# NMX-202.net
KiCad netlist of a schematic drawn in EAGLE
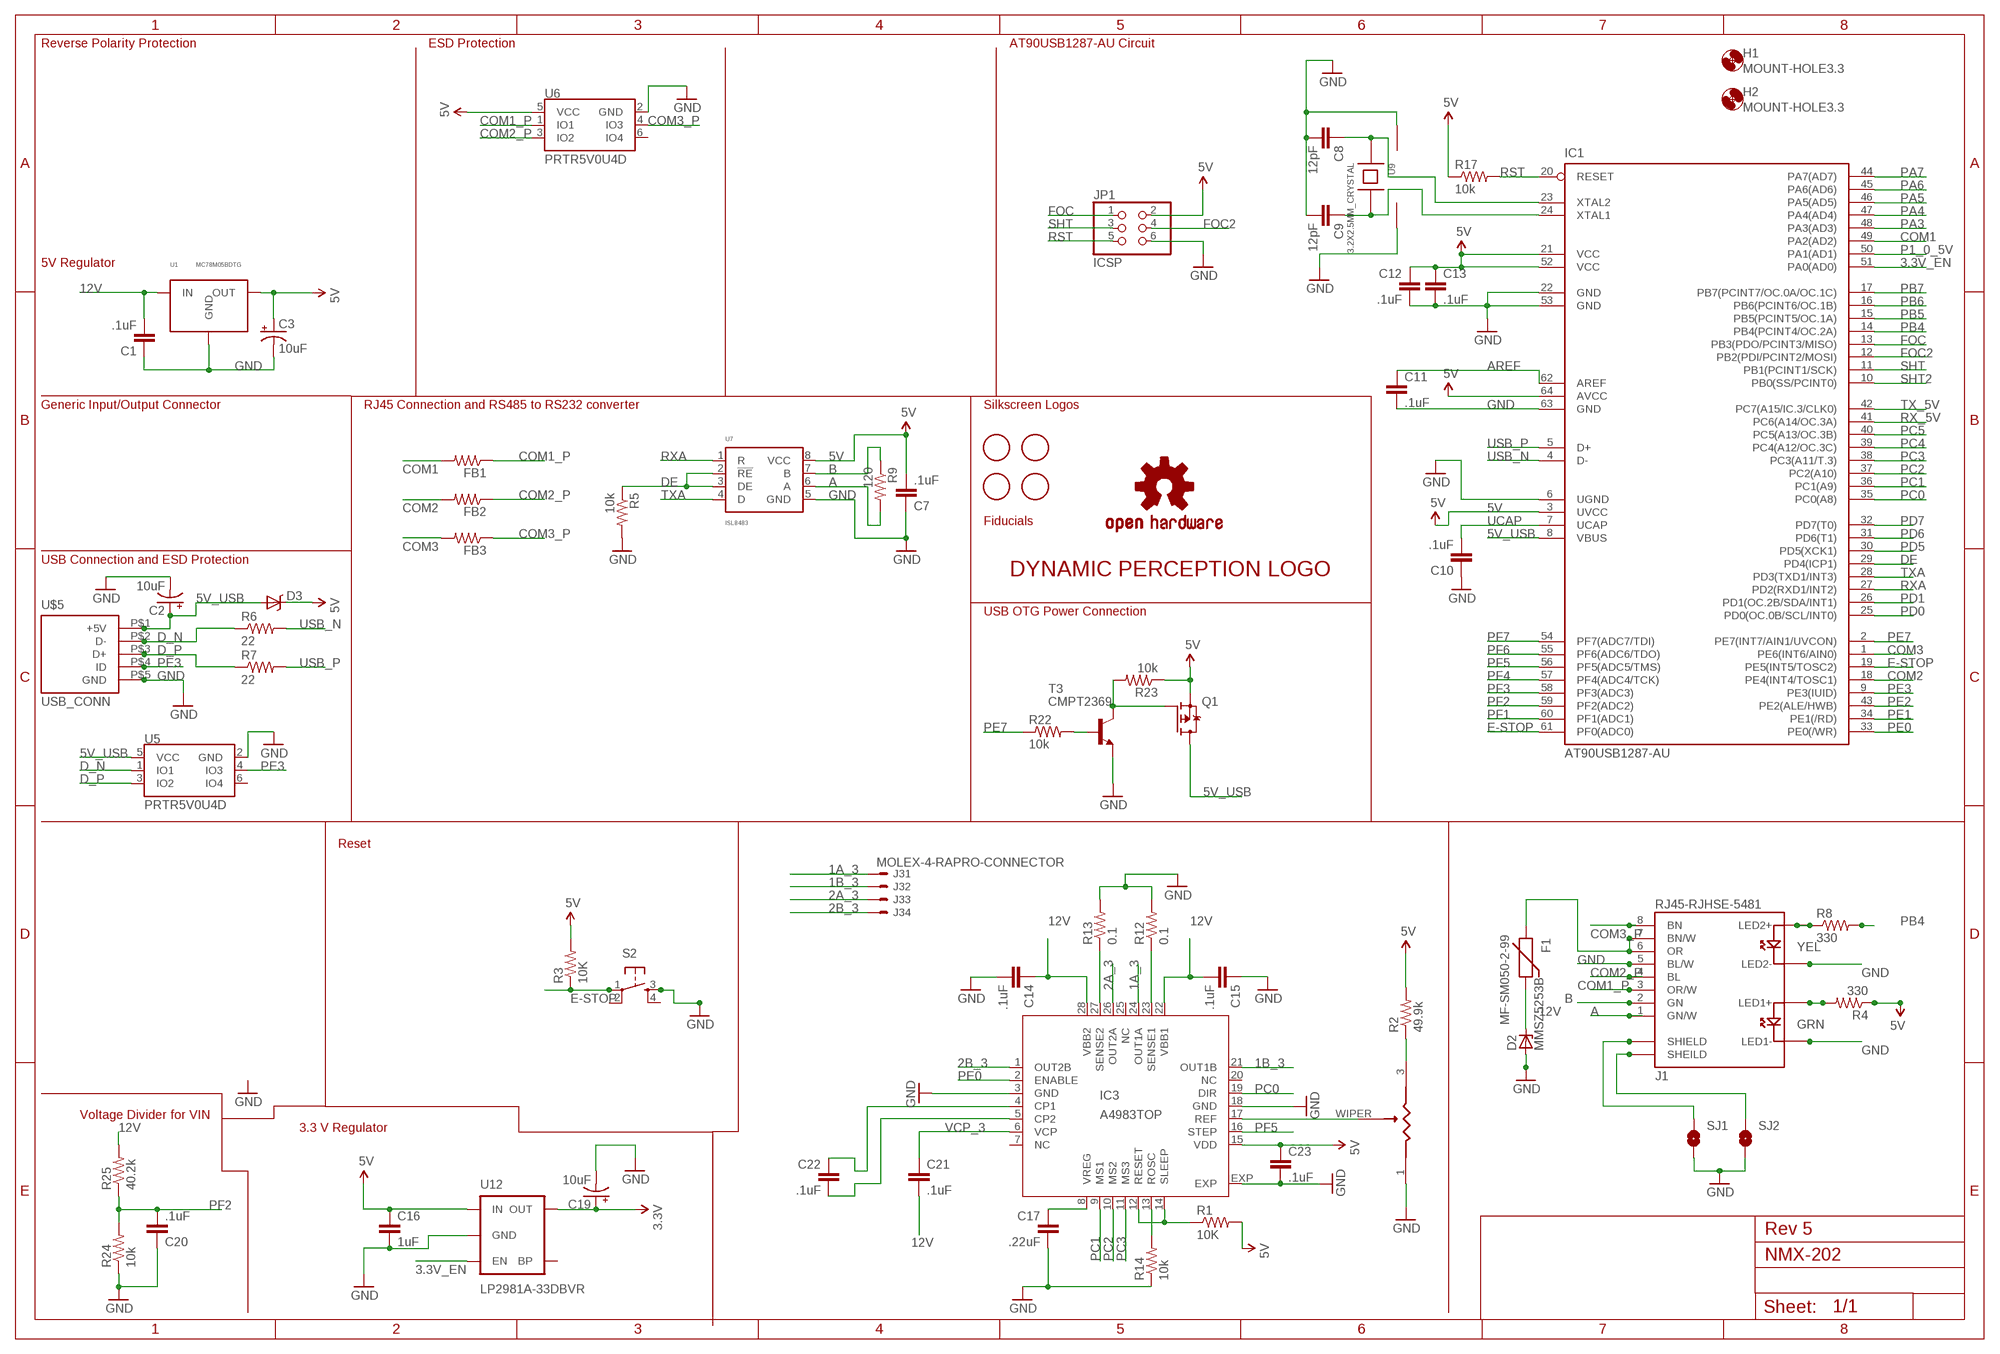
[diagram p0: schematic, sheet 1]

(export (version "E")
  (design (tool "Eeschema 10.0.6"))
  (components
    (comp (ref "C1")
      (value ".1uF")
      (footprint "eagle-import:0402-CAP")
      (fields (field (name "MF") "Taiyo Yuden") (field (name "MPN") "TMK105BJ104KV-F"))
      (libsource (lib "eagle-import") (part "CAP0402-CAP"))
    )
    (comp (ref "C2")
      (value "10uF")
      (footprint "eagle-import:EIA3216")
      (fields (field (name "MF") "Kemet") (field (name "MPN") "T491A106M016AT"))
      (libsource (lib "eagle-import") (part "CAP_POL1206"))
    )
    (comp (ref "C3")
      (value "10uF")
      (footprint "eagle-import:EIA3216")
      (fields (field (name "MF") "Kemet") (field (name "MPN") "T491A106M016AT"))
      (libsource (lib "eagle-import") (part "CAP_POL1206"))
    )
    (comp (ref "C7")
      (value ".1uF")
      (footprint "eagle-import:0402-CAP")
      (fields (field (name "MF") "Taiyo Yuden") (field (name "MPN") "TMK105BJ104KV-F"))
      (libsource (lib "eagle-import") (part "CAP0402-CAP"))
    )
    (comp (ref "C8")
      (value "12pF")
      (footprint "eagle-import:0402-CAP")
      (fields (field (name "MF") "TDK Corporation") (field (name "MPN") "C1005C0G1H120J050BA"))
      (libsource (lib "eagle-import") (part "CAP0402-CAP"))
    )
    (comp (ref "C9")
      (value "12pF")
      (footprint "eagle-import:0402-CAP")
      (fields (field (name "MF") "TDK Corporation") (field (name "MPN") "C1005C0G1H120J050BA"))
      (libsource (lib "eagle-import") (part "CAP0402-CAP"))
    )
    (comp (ref "C10")
      (value ".1uF")
      (footprint "eagle-import:0402-CAP")
      (fields (field (name "MF") "Taiyo Yuden") (field (name "MPN") "TMK105BJ104KV-F"))
      (libsource (lib "eagle-import") (part "CAP0402-CAP"))
    )
    (comp (ref "C11")
      (value ".1uF")
      (footprint "eagle-import:0402-CAP")
      (fields (field (name "MF") "Taiyo Yuden") (field (name "MPN") "TMK105BJ104KV-F"))
      (libsource (lib "eagle-import") (part "CAP0402-CAP"))
    )
    (comp (ref "C12")
      (value ".1uF")
      (footprint "eagle-import:0402-CAP")
      (fields (field (name "MF") "Taiyo Yuden") (field (name "MPN") "TMK105BJ104KV-F"))
      (libsource (lib "eagle-import") (part "CAP0402-CAP"))
    )
    (comp (ref "C13")
      (value ".1uF")
      (footprint "eagle-import:0402-CAP")
      (fields (field (name "MF") "Taiyo Yuden") (field (name "MPN") "TMK105BJ104KV-F"))
      (libsource (lib "eagle-import") (part "CAP0402-CAP"))
    )
    (comp (ref "C14")
      (value ".1uF")
      (footprint "eagle-import:0402-CAP")
      (fields (field (name "MF") "Taiyo Yuden") (field (name "MPN") "TMK105BJ104KV-F"))
      (libsource (lib "eagle-import") (part "CAP0402-CAP"))
    )
    (comp (ref "C15")
      (value ".1uF")
      (footprint "eagle-import:0402-CAP")
      (fields (field (name "MF") "Taiyo Yuden") (field (name "MPN") "TMK105BJ104KV-F"))
      (libsource (lib "eagle-import") (part "CAP0402-CAP"))
    )
    (comp (ref "C16")
      (value "1uF")
      (footprint "eagle-import:0402-CAP")
      (fields (field (name "MF") "TDK Corporation") (field (name "MPN") "C1005X5R1C105K050BC"))
      (libsource (lib "eagle-import") (part "CAP0402-CAP"))
    )
    (comp (ref "C17")
      (value ".22uF")
      (footprint "eagle-import:0402-CAP")
      (fields (field (name "MF") "Taiyo Yuden") (field (name "MPN") "TMK105BJ224KVHF"))
      (libsource (lib "eagle-import") (part "CAP0402-CAP"))
    )
    (comp (ref "C19")
      (value "10uF")
      (footprint "eagle-import:EIA3216")
      (fields (field (name "MF") "Kemet") (field (name "MPN") "T491A106M016AT"))
      (libsource (lib "eagle-import") (part "CAP_POL1206"))
    )
    (comp (ref "C20")
      (value ".1uF")
      (footprint "eagle-import:0402-CAP")
      (fields (field (name "MF") "Taiyo Yuden") (field (name "MPN") "TMK105BJ104KV-F"))
      (libsource (lib "eagle-import") (part "CAP0402-CAP"))
    )
    (comp (ref "C21")
      (value ".1uF")
      (footprint "eagle-import:0402-CAP")
      (fields (field (name "MF") "Taiyo Yuden") (field (name "MPN") "TMK105BJ104KV-F"))
      (libsource (lib "eagle-import") (part "CAP0402-CAP"))
    )
    (comp (ref "C22")
      (value ".1uF")
      (footprint "eagle-import:0402-CAP")
      (fields (field (name "MF") "Taiyo Yuden") (field (name "MPN") "TMK105BJ104KV-F"))
      (libsource (lib "eagle-import") (part "CAP0402-CAP"))
    )
    (comp (ref "C23")
      (value ".1uF")
      (footprint "eagle-import:0402-CAP")
      (fields (field (name "MF") "Taiyo Yuden") (field (name "MPN") "TMK105BJ104KV-F"))
      (libsource (lib "eagle-import") (part "CAP0402-CAP"))
    )
    (comp (ref "D2")
      (value "MMSZ5253B")
      (footprint "eagle-import:SOD123")
      (fields (field (name "MF") "Fairchild Semiconductor"))
      (libsource (lib "eagle-import") (part "ZENER-DIODESOD123"))
    )
    (comp (ref "D3")
      (value "DIODE-SCHOTTKY-BAT20J")
      (footprint "eagle-import:SOD-323")
      (fields (field (name "MF") "NXP Semiconductors") (field (name "MPN") "PMEG3010BEA,115"))
      (libsource (lib "eagle-import") (part "DIODE-SCHOTTKY-BAT20J"))
    )
    (comp (ref "F1")
      (value "MF-SM050-2-99")
      (footprint "eagle-import:PTC-2920")
      (fields (field (name "MF") "Bel Fuse") (field (name "MPN") "0ZCD0050FF2C"))
      (libsource (lib "eagle-import") (part "PTC2920"))
    )
    (comp (ref "FB1")
      (value "HZ0402B102R-10")
      (footprint "eagle-import:R0402")
      (fields (field (name "MF") "Laird-Signal Integrity Products"))
      (libsource (lib "eagle-import") (part "R-US_R0402"))
    )
    (comp (ref "FB2")
      (value "HZ0402B102R-10")
      (footprint "eagle-import:R0402")
      (fields (field (name "MF") "Laird-Signal Integrity Products"))
      (libsource (lib "eagle-import") (part "R-US_R0402"))
    )
    (comp (ref "FB3")
      (value "HZ0402B102R-10")
      (footprint "eagle-import:R0402")
      (fields (field (name "MF") "Laird-Signal Integrity Products"))
      (libsource (lib "eagle-import") (part "R-US_R0402"))
    )
    (comp (ref "FRAME2")
      (value "A3L-LOCSILK_SCREEN")
      (footprint "eagle-import:DRAWING_NAME")
      (libsource (lib "eagle-import") (part "A3L-LOCSILK_SCREEN"))
    )
    (comp (ref "H1")
      (value "MOUNT-HOLE3.3")
      (footprint "eagle-import:3,3")
      (libsource (lib "eagle-import") (part "MOUNT-HOLE3.3"))
    )
    (comp (ref "H2")
      (value "MOUNT-HOLE3.3")
      (footprint "eagle-import:3,3")
      (libsource (lib "eagle-import") (part "MOUNT-HOLE3.3"))
    )
    (comp (ref "IC1")
      (value "AT90USB1287-AU")
      (footprint "eagle-import:TQFP64")
      (fields (field (name "MF") "Atmel"))
      (libsource (lib "eagle-import") (part "AT90USB1287-AU"))
    )
    (comp (ref "IC3")
      (value "A4983TOP")
      (footprint "eagle-import:QFN28ET")
      (fields (field (name "MPN") "A4983SETTR-T") (field (name "MPN_1") "A4983SETTR-T"))
      (libsource (lib "eagle-import") (part "A4983TOP"))
    )
    (comp (ref "J1")
      (value "RJ45-RJHSE-5481")
      (footprint "eagle-import:RJ45-RJHSE")
      (libsource (lib "eagle-import") (part "RJ45-RJHSE-5481"))
    )
    (comp (ref "J3")
      (value "MOLEX-4-RAPRO-CONNECTOR")
      (footprint "eagle-import:PRO_CONNECTOR")
      (fields (field (name "MF") "Molex Inc") (field (name "MPN") "0022053041"))
      (libsource (lib "eagle-import") (part "MOLEX-4-RAPRO-CONNECTOR"))
    )
    (comp (ref "JP1")
      (value "ICSP")
      (footprint "eagle-import:2X03")
      (fields (field (name "MF") "FCI") (field (name "MPN") "67996-406HLF"))
      (libsource (lib "eagle-import") (part "PINHD-2X3"))
    )
    (comp (ref "Q1")
      (value "P-CHANNEL_MOSFET")
      (footprint "eagle-import:SOT23-3")
      (fields (field (name "MF") "Fairchild Semiconductor") (field (name "MPN") "FDV304P"))
      (libsource (lib "eagle-import") (part "P-CHANNEL_MOSFET"))
    )
    (comp (ref "R1")
      (value "10K")
      (footprint "eagle-import:R0402_BOTTOM")
      (fields (field (name "MF") "Yageo") (field (name "MPN") "RC0402FR-0710KL"))
      (libsource (lib "eagle-import") (part "R-US_R0402_B"))
    )
    (comp (ref "R2")
      (value "49.9k")
      (footprint "eagle-import:R0402_BOTTOM")
      (fields (field (name "MF") "Yageo") (field (name "MPN") "RC0402FR-0749K9L"))
      (libsource (lib "eagle-import") (part "R-US_R0402_B"))
    )
    (comp (ref "R3")
      (value "10K")
      (footprint "eagle-import:R0402_BOTTOM")
      (fields (field (name "MF") "Yageo") (field (name "MPN") "RC0402FR-0710KL"))
      (libsource (lib "eagle-import") (part "R-US_R0402_B"))
    )
    (comp (ref "R4")
      (value "330")
      (footprint "eagle-import:R0402")
      (fields (field (name "MF") "Yageo") (field (name "MPN") "RC0402FR-07330RL"))
      (libsource (lib "eagle-import") (part "R-US_R0402"))
    )
    (comp (ref "R5")
      (value "10k")
      (footprint "eagle-import:R0402")
      (fields (field (name "MF") "Yageo") (field (name "MPN") "RC0402FR-0710KL"))
      (libsource (lib "eagle-import") (part "R-US_R0402"))
    )
    (comp (ref "R6")
      (value "22")
      (footprint "eagle-import:R0402")
      (fields (field (name "MF") "Yageo") (field (name "MPN") "RC0402JR-0722RL"))
      (libsource (lib "eagle-import") (part "R-US_R0402"))
    )
    (comp (ref "R7")
      (value "22")
      (footprint "eagle-import:R0402")
      (fields (field (name "MF") "Yageo") (field (name "MPN") "RC0402JR-0722RL"))
      (libsource (lib "eagle-import") (part "R-US_R0402"))
    )
    (comp (ref "R8")
      (value "330")
      (footprint "eagle-import:R0402")
      (fields (field (name "MF") "Yageo") (field (name "MPN") "RC0402FR-07330RL"))
      (libsource (lib "eagle-import") (part "R-US_R0402"))
    )
    (comp (ref "R9")
      (value "120")
      (footprint "eagle-import:R0402")
      (fields (field (name "MF") "Yageo") (field (name "MPN") "RC0402JR-07120RL"))
      (libsource (lib "eagle-import") (part "R-US_R0402"))
    )
    (comp (ref "R12")
      (value "0.1")
      (footprint "eagle-import:R0603")
      (fields (field (name "MF") "Samsung Electro-Mechanics America") (field (name "MPN") "RU1608FR100CS"))
      (libsource (lib "eagle-import") (part "R-US_R0603"))
    )
    (comp (ref "R13")
      (value "0.1")
      (footprint "eagle-import:R0603")
      (fields (field (name "MF") "Samsung Electro-Mechanics America") (field (name "MPN") "RU1608FR100CS"))
      (libsource (lib "eagle-import") (part "R-US_R0603"))
    )
    (comp (ref "R14")
      (value "10k")
      (footprint "eagle-import:R0402_BOTTOM")
      (fields (field (name "MF") "Yageo") (field (name "MPN") "RC0402FR-0720KL"))
      (libsource (lib "eagle-import") (part "R-US_R0402_B"))
    )
    (comp (ref "R17")
      (value "10k")
      (footprint "eagle-import:R0402")
      (fields (field (name "MF") "Yageo") (field (name "MPN") "RC0402FR-0710KL"))
      (libsource (lib "eagle-import") (part "R-US_R0402"))
    )
    (comp (ref "R22")
      (value "10k")
      (footprint "eagle-import:R0402")
      (fields (field (name "MF") "Yageo") (field (name "MPN") "RC0402FR-0710KL"))
      (libsource (lib "eagle-import") (part "R-US_R0402"))
    )
    (comp (ref "R23")
      (value "10k")
      (footprint "eagle-import:R0402")
      (fields (field (name "MF") "Yageo") (field (name "MPN") "RC0402FR-0710KL"))
      (libsource (lib "eagle-import") (part "R-US_R0402"))
    )
    (comp (ref "R24")
      (value "10k")
      (footprint "eagle-import:R0402")
      (fields (field (name "MF") "Yageo") (field (name "MPN") "RC0402FR-0710KL"))
      (libsource (lib "eagle-import") (part "R-US_R0402"))
    )
    (comp (ref "R25")
      (value "40.2k")
      (footprint "eagle-import:R0402")
      (fields (field (name "MF") "Yageo") (field (name "MPN") "RC0402FR-0740K2L"))
      (libsource (lib "eagle-import") (part "R-US_R0402"))
    )
    (comp (ref "S2")
      (value "TAC_SWITCH")
      (footprint "eagle-import:TACTICLE_SWITCH_SMD_EVQP0_BOT")
      (fields (field (name "MF") "Panasonic Electronic Components") (field (name "MPN") "EVQ-P0Q02Q"))
      (libsource (lib "eagle-import") (part "TAC_SWITCH"))
    )
    (comp (ref "SJ1")
      (value "SJ_1WAY")
      (footprint "eagle-import:SJ_2")
      (libsource (lib "eagle-import") (part "SJ_1WAY"))
    )
    (comp (ref "SJ2")
      (value "SJ_1WAY")
      (footprint "eagle-import:SJ_2")
      (libsource (lib "eagle-import") (part "SJ_1WAY"))
    )
    (comp (ref "T3")
      (value "CMPT2369")
      (footprint "eagle-import:SOT23-BEC")
      (fields (field (name "MF") "Fairchild Semiconductor") (field (name "MPN") "BC847BMTF"))
      (libsource (lib "eagle-import") (part "-NPN-SOT23-BECBCW60"))
    )
    (comp (ref "U$1")
      (value "DP_LOGOMICRO")
      (footprint "eagle-import:DP_LOGO_MICRO")
      (libsource (lib "eagle-import") (part "DP_LOGOMICRO"))
    )
    (comp (ref "U$2")
      (value "OSHW-LOGOS")
      (footprint "eagle-import:OSHW-LOGO-S")
      (libsource (lib "eagle-import") (part "OSHW-LOGOS"))
    )
    (comp (ref "U$3")
      (value "FIDUCIAL")
      (footprint "eagle-import:FIDUCIAL_1MM")
      (libsource (lib "eagle-import") (part "FIDUCIAL"))
    )
    (comp (ref "U$4")
      (value "FIDUCIAL")
      (footprint "eagle-import:FIDUCIAL_1MM")
      (libsource (lib "eagle-import") (part "FIDUCIAL"))
    )
    (comp (ref "U$5")
      (value "USB_CONN")
      (footprint "eagle-import:10118194-0001LF")
      (libsource (lib "eagle-import") (part "USB_CONN"))
    )
    (comp (ref "U$6")
      (value "FIDUCIAL")
      (footprint "eagle-import:FIDUCIAL_1MM")
      (libsource (lib "eagle-import") (part "FIDUCIAL"))
    )
    (comp (ref "U$7")
      (value "FIDUCIAL")
      (footprint "eagle-import:FIDUCIAL_1MM")
      (libsource (lib "eagle-import") (part "FIDUCIAL"))
    )
    (comp (ref "U1")
      (value "MC78M05BDTG")
      (footprint "eagle-import:DPAK-3")
      (fields (field (name "MF") "ON Semiconductor") (field (name "MPN") "MC78M05BDTRKG"))
      (libsource (lib "eagle-import") (part "VOLTAGE_REG"))
    )
    (comp (ref "U5")
      (value "PRTR5V0U4D")
      (footprint "eagle-import:SOT23-6")
      (fields (field (name "MF") "NXP Semiconductors"))
      (libsource (lib "eagle-import") (part "PRTR5V0U4D"))
    )
    (comp (ref "U6")
      (value "PRTR5V0U4D")
      (footprint "eagle-import:SOT23-6")
      (fields (field (name "MF") "NXP Semiconductors"))
      (libsource (lib "eagle-import") (part "PRTR5V0U4D"))
    )
    (comp (ref "U7")
      (value "ISL8483")
      (footprint "eagle-import:SO-08")
      (fields
        (field (name "MF") "TEXAS INSTRUMENTS")
        (field (name "MPN") "SN65176BD")
        (field (name "MF_1") "TEXAS INSTRUMENTS")
        (field (name "MPN_1") "SN65176BD")
        (field (name "OC_FARNELL") "9589970")
        (field (name "OC_NEWARK") "08F5891")
      )
      (libsource (lib "eagle-import") (part "SN65176D"))
    )
    (comp (ref "U9")
      (value "3.2X2.5MM_CRYSTAL")
      (footprint "eagle-import:3.2X2.5MM")
      (fields (field (name "MF") "AVX Corp/Kyocera Corp") (field (name "MPN") "CX3225SB16000E0FPZ25"))
      (libsource (lib "eagle-import") (part "3.2X2.5MM_CRYSTAL"))
    )
    (comp (ref "U11")
      (value "CADJ")
      (footprint "eagle-import:3MM_SMD")
      (fields (field (name "MF") "Bourns Inc") (field (name "MPN") "TC33X-2-103E"))
      (libsource (lib "eagle-import") (part "TC33X-2"))
    )
    (comp (ref "U12")
      (value "LP2981A-33DBVR")
      (footprint "eagle-import:SOT23-5")
      (fields (field (name "MF") "Texas Instruments"))
      (libsource (lib "eagle-import") (part "V_REG_LDOSMD"))
    )
  )
  (nets
    (net (code "1") (name "/1A_3") (class "Default")
      (node (ref "IC3") (pin "24") (pinfunction "OUT1A_24") (pintype "output"))
      (node (ref "J3") (pin "P$1") (pinfunction "S_P$1") (pintype "passive"))
    )
    (net (code "2") (name "/1B_3") (class "Default")
      (node (ref "IC3") (pin "21") (pinfunction "OUT1B_21") (pintype "output"))
      (node (ref "J3") (pin "P$2") (pinfunction "S_P$2") (pintype "passive"))
    )
    (net (code "3") (name "/2A_3") (class "Default")
      (node (ref "IC3") (pin "26") (pinfunction "OUT2A_26") (pintype "output"))
      (node (ref "J3") (pin "P$3") (pinfunction "S_P$3") (pintype "passive"))
    )
    (net (code "4") (name "/2B_3") (class "Default")
      (node (ref "IC3") (pin "1") (pinfunction "OUT2B_1") (pintype "output"))
      (node (ref "J3") (pin "P$4") (pinfunction "S_P$4") (pintype "passive"))
    )
    (net (code "5") (name "/3.3V_EN") (class "Default")
      (node (ref "IC1") (pin "51") (pinfunction "PA0(AD0)_51") (pintype "bidirectional"))
      (node (ref "U12") (pin "3") (pinfunction "EN_3") (pintype "input"))
    )
    (net (code "6") (name "/5V_USB") (class "Default")
      (node (ref "C2") (pin "A") (pinfunction "+_A") (pintype "passive"))
      (node (ref "D3") (pin "A") (pinfunction "A_A") (pintype "passive"))
      (node (ref "IC1") (pin "8") (pinfunction "VBUS_8") (pintype "power_in"))
      (node (ref "Q1") (pin "D") (pinfunction "D_D") (pintype "passive"))
      (node (ref "U$5") (pin "P$1") (pinfunction "+5V_P$1") (pintype "bidirectional"))
      (node (ref "U5") (pin "5") (pinfunction "VCC_5") (pintype "power_in"))
    )
    (net (code "7") (name "/12V") (class "Default")
      (node (ref "C1") (pin "2") (pinfunction "2_2") (pintype "passive"))
      (node (ref "C14") (pin "1") (pinfunction "1_1") (pintype "passive"))
      (node (ref "C15") (pin "2") (pinfunction "2_2") (pintype "passive"))
      (node (ref "C21") (pin "2") (pinfunction "2_2") (pintype "passive"))
      (node (ref "D2") (pin "C") (pinfunction "C_C") (pintype "passive"))
      (node (ref "F1") (pin "P$2") (pinfunction "2_P$2") (pintype "bidirectional"))
      (node (ref "IC3") (pin "22") (pinfunction "VBB1_22") (pintype "power_in"))
      (node (ref "IC3") (pin "28") (pinfunction "VBB2_28") (pintype "power_in"))
      (node (ref "R25") (pin "2") (pinfunction "2_2") (pintype "passive"))
      (node (ref "U1") (pin "1") (pinfunction "IN_1") (pintype "bidirectional"))
    )
    (net (code "8") (name "/A") (class "Default")
      (node (ref "J1") (pin "1") (pinfunction "GN/W_1") (pintype "bidirectional"))
      (node (ref "R9") (pin "2") (pinfunction "2_2") (pintype "passive"))
      (node (ref "U7") (pin "6") (pinfunction "A_6") (pintype "input"))
    )
    (net (code "9") (name "/AREF") (class "Default")
      (node (ref "C11") (pin "1") (pinfunction "1_1") (pintype "passive"))
      (node (ref "IC1") (pin "62") (pinfunction "AREF_62") (pintype "bidirectional"))
    )
    (net (code "10") (name "/B") (class "Default")
      (node (ref "J1") (pin "2") (pinfunction "GN_2") (pintype "bidirectional"))
      (node (ref "R9") (pin "1") (pinfunction "1_1") (pintype "passive"))
      (node (ref "U7") (pin "7") (pinfunction "B_7") (pintype "input"))
    )
    (net (code "11") (name "/COM1") (class "Default")
      (node (ref "FB1") (pin "2") (pinfunction "2_2") (pintype "passive"))
      (node (ref "IC1") (pin "49") (pinfunction "PA2(AD2)_49") (pintype "bidirectional"))
    )
    (net (code "12") (name "/COM1_P") (class "Default")
      (node (ref "FB1") (pin "1") (pinfunction "1_1") (pintype "passive"))
      (node (ref "J1") (pin "3") (pinfunction "OR/W_3") (pintype "bidirectional"))
      (node (ref "U6") (pin "1") (pinfunction "IO1_1") (pintype "bidirectional"))
    )
    (net (code "13") (name "/COM2") (class "Default")
      (node (ref "FB2") (pin "2") (pinfunction "2_2") (pintype "passive"))
      (node (ref "IC1") (pin "18") (pinfunction "PE4(INT4/TOSC1)_18") (pintype "bidirectional"))
    )
    (net (code "14") (name "/COM2_P") (class "Default")
      (node (ref "FB2") (pin "1") (pinfunction "1_1") (pintype "passive"))
      (node (ref "J1") (pin "4") (pinfunction "BL_4") (pintype "bidirectional"))
      (node (ref "U6") (pin "3") (pinfunction "IO2_3") (pintype "bidirectional"))
    )
    (net (code "15") (name "/COM3") (class "Default")
      (node (ref "FB3") (pin "2") (pinfunction "2_2") (pintype "passive"))
      (node (ref "IC1") (pin "1") (pinfunction "PE6(INT6/AIN0)_1") (pintype "bidirectional"))
    )
    (net (code "16") (name "/COM3_P") (class "Default")
      (node (ref "FB3") (pin "1") (pinfunction "1_1") (pintype "passive"))
      (node (ref "J1") (pin "8") (pinfunction "BN_8") (pintype "bidirectional"))
      (node (ref "U6") (pin "4") (pinfunction "IO3_4") (pintype "bidirectional"))
    )
    (net (code "17") (name "/DE") (class "Default")
      (node (ref "IC1") (pin "29") (pinfunction "PD4(ICP1)_29") (pintype "bidirectional"))
      (node (ref "R5") (pin "1") (pinfunction "1_1") (pintype "passive"))
      (node (ref "U7") (pin "2") (pinfunction "~{RE}_2") (pintype "input"))
      (node (ref "U7") (pin "3") (pinfunction "DE_3") (pintype "input"))
    )
    (net (code "18") (name "/D_N") (class "Default")
      (node (ref "R6") (pin "1") (pinfunction "1_1") (pintype "passive"))
      (node (ref "U$5") (pin "P$2") (pinfunction "D-_P$2") (pintype "bidirectional"))
      (node (ref "U5") (pin "1") (pinfunction "IO1_1") (pintype "bidirectional"))
    )
    (net (code "19") (name "/D_P") (class "Default")
      (node (ref "R7") (pin "1") (pinfunction "1_1") (pintype "passive"))
      (node (ref "U$5") (pin "P$3") (pinfunction "D+_P$3") (pintype "bidirectional"))
      (node (ref "U5") (pin "3") (pinfunction "IO2_3") (pintype "bidirectional"))
    )
    (net (code "20") (name "/E-STOP") (class "Default")
      (node (ref "IC1") (pin "19") (pinfunction "PE5(INT5/TOSC2)_19") (pintype "bidirectional"))
      (node (ref "IC1") (pin "61") (pinfunction "PF0(ADC0)_61") (pintype "bidirectional"))
      (node (ref "R3") (pin "1") (pinfunction "1_1") (pintype "passive"))
      (node (ref "S2") (pin "1") (pinfunction "1_1") (pintype "passive"))
    )
    (net (code "21") (name "/FOC") (class "Default")
      (node (ref "IC1") (pin "13") (pinfunction "PB3(PDO/PCINT3/MISO)_13") (pintype "bidirectional"))
      (node (ref "JP1") (pin "1") (pinfunction "1_1") (pintype "passive"))
    )
    (net (code "22") (name "/FOC2") (class "Default")
      (node (ref "IC1") (pin "12") (pinfunction "PB2(PDI/PCINT2/MOSI)_12") (pintype "bidirectional"))
      (node (ref "JP1") (pin "4") (pinfunction "4_4") (pintype "passive"))
    )
    (net (code "23") (name "/P1_0_5V") (class "Default")
      (node (ref "IC1") (pin "50") (pinfunction "PA1(AD1)_50") (pintype "bidirectional"))
    )
    (net (code "24") (name "/PA3") (class "Default")
      (node (ref "IC1") (pin "48") (pinfunction "PA3(AD3)_48") (pintype "bidirectional"))
    )
    (net (code "25") (name "/PA4") (class "Default")
      (node (ref "IC1") (pin "47") (pinfunction "PA4(AD4)_47") (pintype "bidirectional"))
    )
    (net (code "26") (name "/PA5") (class "Default")
      (node (ref "IC1") (pin "46") (pinfunction "PA5(AD5)_46") (pintype "bidirectional"))
    )
    (net (code "27") (name "/PA6") (class "Default")
      (node (ref "IC1") (pin "45") (pinfunction "PA6(AD6)_45") (pintype "bidirectional"))
    )
    (net (code "28") (name "/PA7") (class "Default")
      (node (ref "IC1") (pin "44") (pinfunction "PA7(AD7)_44") (pintype "bidirectional"))
    )
    (net (code "29") (name "/PB4") (class "Default")
      (node (ref "IC1") (pin "14") (pinfunction "PB4(PCINT4/OC.2A)_14") (pintype "bidirectional"))
      (node (ref "R8") (pin "2") (pinfunction "2_2") (pintype "passive"))
    )
    (net (code "30") (name "/PB5") (class "Default")
      (node (ref "IC1") (pin "15") (pinfunction "PB5(PCINT5/OC.1A)_15") (pintype "bidirectional"))
    )
    (net (code "31") (name "/PB6") (class "Default")
      (node (ref "IC1") (pin "16") (pinfunction "PB6(PCINT6/OC.1B)_16") (pintype "bidirectional"))
    )
    (net (code "32") (name "/PB7") (class "Default")
      (node (ref "IC1") (pin "17") (pinfunction "PB7(PCINT7/OC.0A/OC.1C)_17") (pintype "bidirectional"))
    )
    (net (code "33") (name "/PC0") (class "Default")
      (node (ref "IC1") (pin "35") (pinfunction "PC0(A8)_35") (pintype "bidirectional"))
      (node (ref "IC3") (pin "19") (pinfunction "DIR_19") (pintype "input"))
    )
    (net (code "34") (name "/PC1") (class "Default")
      (node (ref "IC1") (pin "36") (pinfunction "PC1(A9)_36") (pintype "bidirectional"))
      (node (ref "IC3") (pin "9") (pinfunction "MS1_9") (pintype "input"))
    )
    (net (code "35") (name "/PC2") (class "Default")
      (node (ref "IC1") (pin "37") (pinfunction "PC2(A10)_37") (pintype "bidirectional"))
      (node (ref "IC3") (pin "10") (pinfunction "MS2_10") (pintype "input"))
    )
    (net (code "36") (name "/PC3") (class "Default")
      (node (ref "IC1") (pin "38") (pinfunction "PC3(A11/T.3)_38") (pintype "bidirectional"))
      (node (ref "IC3") (pin "11") (pinfunction "MS3_11") (pintype "input"))
    )
    (net (code "37") (name "/PC4") (class "Default")
      (node (ref "IC1") (pin "39") (pinfunction "PC4(A12/OC.3C)_39") (pintype "bidirectional"))
    )
    (net (code "38") (name "/PC5") (class "Default")
      (node (ref "IC1") (pin "40") (pinfunction "PC5(A13/OC.3B)_40") (pintype "bidirectional"))
    )
    (net (code "39") (name "/PD0") (class "Default")
      (node (ref "IC1") (pin "25") (pinfunction "PD0(OC.0B/SCL/INT0)_25") (pintype "bidirectional"))
    )
    (net (code "40") (name "/PD1") (class "Default")
      (node (ref "IC1") (pin "26") (pinfunction "PD1(OC.2B/SDA/INT1)_26") (pintype "bidirectional"))
    )
    (net (code "41") (name "/PD5") (class "Default")
      (node (ref "IC1") (pin "30") (pinfunction "PD5(XCK1)_30") (pintype "bidirectional"))
    )
    (net (code "42") (name "/PD6") (class "Default")
      (node (ref "IC1") (pin "31") (pinfunction "PD6(T1)_31") (pintype "bidirectional"))
    )
    (net (code "43") (name "/PD7") (class "Default")
      (node (ref "IC1") (pin "32") (pinfunction "PD7(T0)_32") (pintype "bidirectional"))
    )
    (net (code "44") (name "/PE0") (class "Default")
      (node (ref "IC1") (pin "33") (pinfunction "PE0(/WR)_33") (pintype "bidirectional"))
      (node (ref "IC3") (pin "2") (pinfunction "ENABLE_2") (pintype "input"))
    )
    (net (code "45") (name "/PE1") (class "Default")
      (node (ref "IC1") (pin "34") (pinfunction "PE1(/RD)_34") (pintype "bidirectional"))
    )
    (net (code "46") (name "/PE2") (class "Default")
      (node (ref "IC1") (pin "43") (pinfunction "PE2(ALE/HWB)_43") (pintype "bidirectional"))
    )
    (net (code "47") (name "/PE3") (class "Default")
      (node (ref "IC1") (pin "9") (pinfunction "PE3(IUID)_9") (pintype "bidirectional"))
      (node (ref "U$5") (pin "P$4") (pinfunction "ID_P$4") (pintype "bidirectional"))
      (node (ref "U5") (pin "4") (pinfunction "IO3_4") (pintype "bidirectional"))
    )
    (net (code "48") (name "/PE7") (class "Default")
      (node (ref "IC1") (pin "2") (pinfunction "PE7(INT7/AIN1/UVCON)_2") (pintype "bidirectional"))
      (node (ref "R22") (pin "1") (pinfunction "1_1") (pintype "passive"))
    )
    (net (code "49") (name "/PF1") (class "Default")
      (node (ref "IC1") (pin "60") (pinfunction "PF1(ADC1)_60") (pintype "bidirectional"))
    )
    (net (code "50") (name "/PF2") (class "Default")
      (node (ref "C20") (pin "2") (pinfunction "2_2") (pintype "passive"))
      (node (ref "IC1") (pin "59") (pinfunction "PF2(ADC2)_59") (pintype "bidirectional"))
      (node (ref "R24") (pin "2") (pinfunction "2_2") (pintype "passive"))
      (node (ref "R25") (pin "1") (pinfunction "1_1") (pintype "passive"))
    )
    (net (code "51") (name "/PF3") (class "Default")
      (node (ref "IC1") (pin "58") (pinfunction "PF3(ADC3)_58") (pintype "bidirectional"))
    )
    (net (code "52") (name "/PF4") (class "Default")
      (node (ref "IC1") (pin "57") (pinfunction "PF4(ADC4/TCK)_57") (pintype "bidirectional"))
    )
    (net (code "53") (name "/PF5") (class "Default")
      (node (ref "IC1") (pin "56") (pinfunction "PF5(ADC5/TMS)_56") (pintype "bidirectional"))
      (node (ref "IC3") (pin "16") (pinfunction "STEP_16") (pintype "input"))
    )
    (net (code "54") (name "/PF6") (class "Default")
      (node (ref "IC1") (pin "55") (pinfunction "PF6(ADC6/TDO)_55") (pintype "bidirectional"))
    )
    (net (code "55") (name "/PF7") (class "Default")
      (node (ref "IC1") (pin "54") (pinfunction "PF7(ADC7/TDI)_54") (pintype "bidirectional"))
    )
    (net (code "56") (name "/RST") (class "Default")
      (node (ref "IC1") (pin "20") (pinfunction "RESET_20") (pintype "input"))
      (node (ref "JP1") (pin "5") (pinfunction "5_5") (pintype "passive"))
      (node (ref "R17") (pin "2") (pinfunction "2_2") (pintype "passive"))
    )
    (net (code "57") (name "/RXA") (class "Default")
      (node (ref "IC1") (pin "27") (pinfunction "PD2(RXD1/INT2)_27") (pintype "bidirectional"))
      (node (ref "U7") (pin "1") (pinfunction "R_1") (pintype "input"))
    )
    (net (code "58") (name "/RX_5V") (class "Default")
      (node (ref "IC1") (pin "41") (pinfunction "PC6(A14/OC.3A)_41") (pintype "bidirectional"))
    )
    (net (code "59") (name "/SHT") (class "Default")
      (node (ref "IC1") (pin "11") (pinfunction "PB1(PCINT1/SCK)_11") (pintype "bidirectional"))
      (node (ref "JP1") (pin "3") (pinfunction "3_3") (pintype "passive"))
    )
    (net (code "60") (name "/SHT2") (class "Default")
      (node (ref "IC1") (pin "10") (pinfunction "PB0(SS/PCINT0)_10") (pintype "bidirectional"))
    )
    (net (code "61") (name "/TXA") (class "Default")
      (node (ref "IC1") (pin "28") (pinfunction "PD3(TXD1/INT3)_28") (pintype "bidirectional"))
      (node (ref "U7") (pin "4") (pinfunction "D_4") (pintype "input"))
    )
    (net (code "62") (name "/TX_5V") (class "Default")
      (node (ref "IC1") (pin "42") (pinfunction "PC7(A15/IC.3/CLK0)_42") (pintype "bidirectional"))
    )
    (net (code "63") (name "/UCAP") (class "Default")
      (node (ref "C10") (pin "2") (pinfunction "2_2") (pintype "passive"))
      (node (ref "IC1") (pin "7") (pinfunction "UCAP_7") (pintype "power_in"))
    )
    (net (code "64") (name "/USB_N") (class "Default")
      (node (ref "IC1") (pin "4") (pinfunction "D-_4") (pintype "bidirectional"))
      (node (ref "R6") (pin "2") (pinfunction "2_2") (pintype "passive"))
    )
    (net (code "65") (name "/USB_P") (class "Default")
      (node (ref "IC1") (pin "5") (pinfunction "D+_5") (pintype "bidirectional"))
      (node (ref "R7") (pin "2") (pinfunction "2_2") (pintype "passive"))
    )
    (net (code "66") (name "/VCP_3") (class "Default")
      (node (ref "C21") (pin "1") (pinfunction "1_1") (pintype "passive"))
      (node (ref "IC3") (pin "6") (pinfunction "VCP_6") (pintype "passive"))
    )
    (net (code "67") (name "3.3V") (class "Default")
      (node (ref "C19") (pin "A") (pinfunction "+_A") (pintype "passive"))
      (node (ref "U12") (pin "5") (pinfunction "OUT_5") (pintype "passive"))
    )
    (net (code "68") (name "5V") (class "Default")
      (node (ref "C12") (pin "1") (pinfunction "1_1") (pintype "passive"))
      (node (ref "C13") (pin "1") (pinfunction "1_1") (pintype "passive"))
      (node (ref "C16") (pin "1") (pinfunction "1_1") (pintype "passive"))
      (node (ref "C23") (pin "1") (pinfunction "1_1") (pintype "passive"))
      (node (ref "C3") (pin "A") (pinfunction "+_A") (pintype "passive"))
      (node (ref "C7") (pin "2") (pinfunction "2_2") (pintype "passive"))
      (node (ref "D3") (pin "C") (pinfunction "C_C") (pintype "passive"))
      (node (ref "IC1") (pin "21") (pinfunction "VCC_21") (pintype "power_in"))
      (node (ref "IC1") (pin "3") (pinfunction "UVCC_3") (pintype "power_in"))
      (node (ref "IC1") (pin "52") (pinfunction "VCC_52") (pintype "power_in"))
      (node (ref "IC1") (pin "64") (pinfunction "AVCC_64") (pintype "bidirectional"))
      (node (ref "IC3") (pin "15") (pinfunction "VDD_15") (pintype "power_in"))
      (node (ref "JP1") (pin "2") (pinfunction "2_2") (pintype "passive"))
      (node (ref "Q1") (pin "S") (pinfunction "S_S") (pintype "passive"))
      (node (ref "R1") (pin "2") (pinfunction "2_2") (pintype "passive"))
      (node (ref "R17") (pin "1") (pinfunction "1_1") (pintype "passive"))
      (node (ref "R2") (pin "2") (pinfunction "2_2") (pintype "passive"))
      (node (ref "R23") (pin "1") (pinfunction "1_1") (pintype "passive"))
      (node (ref "R3") (pin "2") (pinfunction "2_2") (pintype "passive"))
      (node (ref "R4") (pin "1") (pinfunction "1_1") (pintype "passive"))
      (node (ref "U1") (pin "2") (pinfunction "OUT_2") (pintype "bidirectional"))
      (node (ref "U12") (pin "1") (pinfunction "IN_1") (pintype "input"))
      (node (ref "U6") (pin "5") (pinfunction "VCC_5") (pintype "power_in"))
      (node (ref "U7") (pin "8") (pinfunction "VCC_8") (pintype "input"))
    )
    (net (code "69") (name "GND") (class "Default")
      (node (ref "C1") (pin "1") (pinfunction "1_1") (pintype "passive"))
      (node (ref "C10") (pin "1") (pinfunction "1_1") (pintype "passive"))
      (node (ref "C11") (pin "2") (pinfunction "2_2") (pintype "passive"))
      (node (ref "C12") (pin "2") (pinfunction "2_2") (pintype "passive"))
      (node (ref "C13") (pin "2") (pinfunction "2_2") (pintype "passive"))
      (node (ref "C14") (pin "2") (pinfunction "2_2") (pintype "passive"))
      (node (ref "C15") (pin "1") (pinfunction "1_1") (pintype "passive"))
      (node (ref "C16") (pin "2") (pinfunction "2_2") (pintype "passive"))
      (node (ref "C17") (pin "2") (pinfunction "2_2") (pintype "passive"))
      (node (ref "C19") (pin "C") (pinfunction "-_C") (pintype "passive"))
      (node (ref "C2") (pin "C") (pinfunction "-_C") (pintype "passive"))
      (node (ref "C20") (pin "1") (pinfunction "1_1") (pintype "passive"))
      (node (ref "C23") (pin "2") (pinfunction "2_2") (pintype "passive"))
      (node (ref "C3") (pin "C") (pinfunction "-_C") (pintype "passive"))
      (node (ref "C7") (pin "1") (pinfunction "1_1") (pintype "passive"))
      (node (ref "C8") (pin "2") (pinfunction "2_2") (pintype "passive"))
      (node (ref "C9") (pin "2") (pinfunction "2_2") (pintype "passive"))
      (node (ref "D2") (pin "A") (pinfunction "A_A") (pintype "passive"))
      (node (ref "IC1") (pin "22") (pinfunction "GND_22") (pintype "power_in"))
      (node (ref "IC1") (pin "53") (pinfunction "GND_53") (pintype "power_in"))
      (node (ref "IC1") (pin "6") (pinfunction "UGND_6") (pintype "power_in"))
      (node (ref "IC1") (pin "63") (pinfunction "GND_63") (pintype "power_in"))
      (node (ref "IC3") (pin "18") (pinfunction "GND_18") (pintype "power_in"))
      (node (ref "IC3") (pin "3") (pinfunction "GND_3") (pintype "power_in"))
      (node (ref "IC3") (pin "EXP") (pinfunction "EXP_EXP") (pintype "passive"))
      (node (ref "J1") (pin "5") (pinfunction "BL/W_5") (pintype "bidirectional"))
      (node (ref "J1") (pin "LE1D-") (pinfunction "LED1-_LE1D-") (pintype "bidirectional"))
      (node (ref "J1") (pin "LED2-") (pinfunction "LED2-_LED2-") (pintype "bidirectional"))
      (node (ref "JP1") (pin "6") (pinfunction "6_6") (pintype "passive"))
      (node (ref "R12") (pin "2") (pinfunction "2_2") (pintype "passive"))
      (node (ref "R13") (pin "2") (pinfunction "2_2") (pintype "passive"))
      (node (ref "R14") (pin "1") (pinfunction "1_1") (pintype "passive"))
      (node (ref "R24") (pin "1") (pinfunction "1_1") (pintype "passive"))
      (node (ref "R5") (pin "2") (pinfunction "2_2") (pintype "passive"))
      (node (ref "S2") (pin "3") (pinfunction "3_3") (pintype "passive"))
      (node (ref "SJ1") (pin "2") (pinfunction "2_2") (pintype "passive"))
      (node (ref "SJ2") (pin "2") (pinfunction "2_2") (pintype "passive"))
      (node (ref "T3") (pin "E") (pinfunction "E_E") (pintype "passive"))
      (node (ref "U$5") (pin "P$5") (pinfunction "GND_P$5") (pintype "bidirectional"))
      (node (ref "U1") (pin "4") (pinfunction "GND_4") (pintype "bidirectional"))
      (node (ref "U11") (pin "1") (pinfunction "1_1") (pintype "bidirectional"))
      (node (ref "U12") (pin "2") (pinfunction "GND_2") (pintype "input"))
      (node (ref "U5") (pin "2") (pinfunction "GND_2") (pintype "power_in"))
      (node (ref "U6") (pin "2") (pinfunction "GND_2") (pintype "power_in"))
      (node (ref "U7") (pin "5") (pinfunction "GND_5") (pintype "input"))
      (node (ref "U9") (pin "2") (pinfunction "GND_2") (pintype "power_in"))
      (node (ref "U9") (pin "4") (pinfunction "4_4") (pintype "power_in"))
    )
    (net (code "70") (name "Net-(F1-1)") (class "Default")
      (node (ref "F1") (pin "P$1") (pinfunction "1_P$1") (pintype "bidirectional"))
      (node (ref "J1") (pin "6") (pinfunction "OR_6") (pintype "bidirectional"))
      (node (ref "J1") (pin "7") (pinfunction "BN/W_7") (pintype "bidirectional"))
    )
    (net (code "71") (name "Net-(IC1-XTAL1)") (class "Default")
      (node (ref "C9") (pin "1") (pinfunction "1_1") (pintype "passive"))
      (node (ref "IC1") (pin "24") (pinfunction "XTAL1_24") (pintype "bidirectional"))
      (node (ref "U9") (pin "3") (pinfunction "3_3") (pintype "bidirectional"))
    )
    (net (code "72") (name "Net-(IC1-XTAL2)") (class "Default")
      (node (ref "C8") (pin "1") (pinfunction "1_1") (pintype "passive"))
      (node (ref "IC1") (pin "23") (pinfunction "XTAL2_23") (pintype "bidirectional"))
      (node (ref "U9") (pin "1") (pinfunction "1_1") (pintype "bidirectional"))
    )
    (net (code "73") (name "Net-(IC3-CP1)") (class "Default")
      (node (ref "C22") (pin "1") (pinfunction "1_1") (pintype "passive"))
      (node (ref "IC3") (pin "4") (pinfunction "CP1_4") (pintype "passive"))
    )
    (net (code "74") (name "Net-(IC3-CP2)") (class "Default")
      (node (ref "C22") (pin "2") (pinfunction "2_2") (pintype "passive"))
      (node (ref "IC3") (pin "5") (pinfunction "CP2_5") (pintype "passive"))
    )
    (net (code "75") (name "Net-(IC3-REF)") (class "Default")
      (node (ref "IC3") (pin "17") (pinfunction "REF_17") (pintype "input"))
      (node (ref "U11") (pin "WIPER") (pinfunction "2_WIPER") (pintype "bidirectional"))
    )
    (net (code "76") (name "Net-(IC3-RESET)") (class "Default")
      (node (ref "IC3") (pin "12") (pinfunction "RESET_12") (pintype "input"))
      (node (ref "IC3") (pin "14") (pinfunction "SLEEP_14") (pintype "input"))
      (node (ref "R1") (pin "1") (pinfunction "1_1") (pintype "passive"))
    )
    (net (code "77") (name "Net-(IC3-ROSC)") (class "Default")
      (node (ref "IC3") (pin "13") (pinfunction "ROSC_13") (pintype "input"))
      (node (ref "R14") (pin "2") (pinfunction "2_2") (pintype "passive"))
    )
    (net (code "78") (name "Net-(IC3-SENSE1)") (class "Default")
      (node (ref "IC3") (pin "23") (pinfunction "SENSE1_23") (pintype "input"))
      (node (ref "R12") (pin "1") (pinfunction "1_1") (pintype "passive"))
    )
    (net (code "79") (name "Net-(IC3-SENSE2)") (class "Default")
      (node (ref "IC3") (pin "27") (pinfunction "SENSE2_27") (pintype "input"))
      (node (ref "R13") (pin "1") (pinfunction "1_1") (pintype "passive"))
    )
    (net (code "80") (name "Net-(IC3-VREG)") (class "Default")
      (node (ref "C17") (pin "1") (pinfunction "1_1") (pintype "passive"))
      (node (ref "IC3") (pin "8") (pinfunction "VREG_8") (pintype "passive"))
    )
    (net (code "81") (name "Net-(J1-PadLED1+)") (class "Default")
      (node (ref "J1") (pin "LED1+") (pinfunction "LED1+_LED1+") (pintype "bidirectional"))
      (node (ref "R4") (pin "2") (pinfunction "2_2") (pintype "passive"))
    )
    (net (code "82") (name "Net-(J1-PadLED2+)") (class "Default")
      (node (ref "J1") (pin "LED2+") (pinfunction "LED2+_LED2+") (pintype "bidirectional"))
      (node (ref "R8") (pin "1") (pinfunction "1_1") (pintype "passive"))
    )
    (net (code "83") (name "Net-(J1-SHEILD)") (class "Default")
      (node (ref "J1") (pin "SHEILD@1") (pinfunction "SHEILD_SHEILD@1") (pintype "bidirectional"))
      (node (ref "SJ2") (pin "1") (pinfunction "1_1") (pintype "passive"))
    )
    (net (code "84") (name "Net-(J1-SHIELD)") (class "Default")
      (node (ref "J1") (pin "SHIELD@0") (pinfunction "SHIELD_SHIELD@0") (pintype "bidirectional"))
      (node (ref "SJ1") (pin "1") (pinfunction "1_1") (pintype "passive"))
    )
    (net (code "85") (name "Net-(Q1-PadG)") (class "Default")
      (node (ref "Q1") (pin "G") (pinfunction "G_G") (pintype "passive"))
      (node (ref "R23") (pin "2") (pinfunction "2_2") (pintype "passive"))
      (node (ref "T3") (pin "C") (pinfunction "C_C") (pintype "passive"))
    )
    (net (code "86") (name "Net-(R2-Pad1)") (class "Default")
      (node (ref "R2") (pin "1") (pinfunction "1_1") (pintype "passive"))
      (node (ref "U11") (pin "3") (pinfunction "3_3") (pintype "bidirectional"))
    )
    (net (code "87") (name "Net-(R22-Pad2)") (class "Default")
      (node (ref "R22") (pin "2") (pinfunction "2_2") (pintype "passive"))
      (node (ref "T3") (pin "B") (pinfunction "B_B") (pintype "passive"))
    )
    (net (code "88") (name "unconnected-(IC3-NC-Pad7)") (class "Default")
      (node (ref "IC3") (pin "7") (pinfunction "NC_7") (pintype "no_connect"))
    )
    (net (code "89") (name "unconnected-(IC3-NC-Pad20)") (class "Default")
      (node (ref "IC3") (pin "20") (pinfunction "NC_20") (pintype "no_connect"))
    )
    (net (code "90") (name "unconnected-(IC3-NC-Pad25)") (class "Default")
      (node (ref "IC3") (pin "25") (pinfunction "NC_25") (pintype "no_connect"))
    )
    (net (code "91") (name "unconnected-(S2-Pad2)") (class "Default")
      (node (ref "S2") (pin "2") (pinfunction "2_2") (pintype "passive"))
    )
    (net (code "92") (name "unconnected-(S2-Pad4)") (class "Default")
      (node (ref "S2") (pin "4") (pinfunction "4_4") (pintype "passive"))
    )
    (net (code "93") (name "unconnected-(U5-IO4-Pad6)") (class "Default")
      (node (ref "U5") (pin "6") (pinfunction "IO4_6") (pintype "bidirectional"))
    )
    (net (code "94") (name "unconnected-(U6-IO4-Pad6)") (class "Default")
      (node (ref "U6") (pin "6") (pinfunction "IO4_6") (pintype "bidirectional"))
    )
    (net (code "95") (name "unconnected-(U12-BP-Pad4)") (class "Default")
      (node (ref "U12") (pin "4") (pinfunction "BP_4") (pintype "input"))
    )
  )
)
